# PentaBlinky.net
KiCad netlist of a schematic drawn in EAGLE
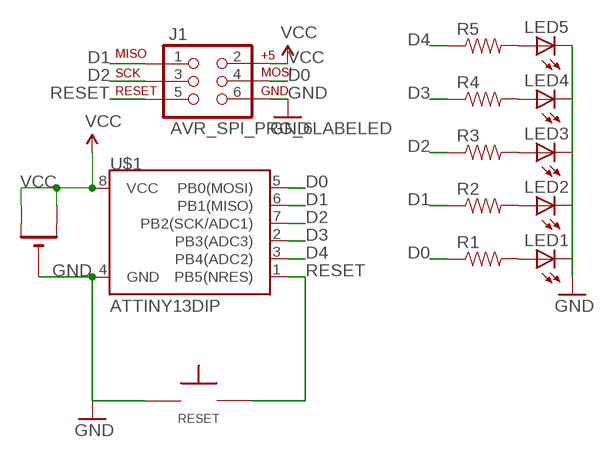
[diagram p0: schematic, sheet 1]

(export (version "E")
  (design (tool "Eeschema 10.0.6"))
  (components
    (comp (ref "J1")
      (value "AVR_SPI_PRG_6LABELED")
      (footprint "eagle-import:2X3-NS")
      (libsource (lib "eagle-import") (part "AVR_SPI_PRG_6LABELED"))
    )
    (comp (ref "LED1")
      (value "LED5MM")
      (footprint "eagle-import:LED5MM")
      (libsource (lib "eagle-import") (part "LED5MM"))
    )
    (comp (ref "LED2")
      (value "LED5MM")
      (footprint "eagle-import:LED5MM")
      (libsource (lib "eagle-import") (part "LED5MM"))
    )
    (comp (ref "LED3")
      (value "LED5MM")
      (footprint "eagle-import:LED5MM")
      (libsource (lib "eagle-import") (part "LED5MM"))
    )
    (comp (ref "LED4")
      (value "LED5MM")
      (footprint "eagle-import:LED5MM")
      (libsource (lib "eagle-import") (part "LED5MM"))
    )
    (comp (ref "LED5")
      (value "LED5MM")
      (footprint "eagle-import:LED5MM")
      (libsource (lib "eagle-import") (part "LED5MM"))
    )
    (comp (ref "R1")
      (value "RESISTORAXIAL-0.3")
      (footprint "eagle-import:AXIAL-0.3")
      (libsource (lib "eagle-import") (part "RESISTORAXIAL-0.3"))
    )
    (comp (ref "R2")
      (value "RESISTORAXIAL-0.3")
      (footprint "eagle-import:AXIAL-0.3")
      (libsource (lib "eagle-import") (part "RESISTORAXIAL-0.3"))
    )
    (comp (ref "R3")
      (value "RESISTORAXIAL-0.3")
      (footprint "eagle-import:AXIAL-0.3")
      (libsource (lib "eagle-import") (part "RESISTORAXIAL-0.3"))
    )
    (comp (ref "R4")
      (value "RESISTORAXIAL-0.3")
      (footprint "eagle-import:AXIAL-0.3")
      (libsource (lib "eagle-import") (part "RESISTORAXIAL-0.3"))
    )
    (comp (ref "R5")
      (value "RESISTORAXIAL-0.3")
      (footprint "eagle-import:AXIAL-0.3")
      (libsource (lib "eagle-import") (part "RESISTORAXIAL-0.3"))
    )
    (comp (ref "RESET")
      (value "SPST_NO")
      (footprint "eagle-import:TAC_SPST_NO")
      (libsource (lib "eagle-import") (part "TAC_SPST_NO"))
    )
    (comp (ref "U$1")
      (value "ATTINY13DIP")
      (footprint "eagle-import:DIP08")
      (libsource (lib "eagle-import") (part "ATTINY13DIP"))
    )
    (comp (ref "U$4")
      (value "BATT_GEN")
      (footprint "eagle-import:AA-AAA")
      (libsource (lib "eagle-import") (part "BATT_GEN"))
    )
  )
  (nets
    (net (code "1") (name "/D0") (class "Default")
      (node (ref "J1") (pin "4") (pinfunction "MOSI_4") (pintype "passive"))
      (node (ref "R1") (pin "P$1") (pinfunction "1_P$1") (pintype "passive"))
      (node (ref "U$1") (pin "5") (pinfunction "PB0(MOSI)_5") (pintype "bidirectional"))
    )
    (net (code "2") (name "/D1") (class "Default")
      (node (ref "J1") (pin "1") (pinfunction "MISO_1") (pintype "passive"))
      (node (ref "R2") (pin "P$1") (pinfunction "1_P$1") (pintype "passive"))
      (node (ref "U$1") (pin "6") (pinfunction "PB1(MISO)_6") (pintype "bidirectional"))
    )
    (net (code "3") (name "/D2") (class "Default")
      (node (ref "J1") (pin "3") (pinfunction "SCK_3") (pintype "passive"))
      (node (ref "R3") (pin "P$1") (pinfunction "1_P$1") (pintype "passive"))
      (node (ref "U$1") (pin "7") (pinfunction "PB2(SCK/ADC1)_7") (pintype "bidirectional"))
    )
    (net (code "4") (name "/D3") (class "Default")
      (node (ref "R4") (pin "P$1") (pinfunction "1_P$1") (pintype "passive"))
      (node (ref "U$1") (pin "2") (pinfunction "PB3(ADC3)_2") (pintype "bidirectional"))
    )
    (net (code "5") (name "/D4") (class "Default")
      (node (ref "R5") (pin "P$1") (pinfunction "1_P$1") (pintype "passive"))
      (node (ref "U$1") (pin "3") (pinfunction "PB4(ADC2)_3") (pintype "bidirectional"))
    )
    (net (code "6") (name "/RESET") (class "Default")
      (node (ref "J1") (pin "5") (pinfunction "RST_5") (pintype "passive"))
      (node (ref "RESET") (pin "P$2") (pinfunction "P$2_P$2") (pintype "bidirectional"))
      (node (ref "U$1") (pin "1") (pinfunction "PB5(NRES)_1") (pintype "bidirectional"))
    )
    (net (code "7") (name "GND") (class "Default")
      (node (ref "J1") (pin "6") (pinfunction "GND_6") (pintype "passive"))
      (node (ref "LED1") (pin "K") (pinfunction "C_K") (pintype "passive"))
      (node (ref "LED2") (pin "K") (pinfunction "C_K") (pintype "passive"))
      (node (ref "LED3") (pin "K") (pinfunction "C_K") (pintype "passive"))
      (node (ref "LED4") (pin "K") (pinfunction "C_K") (pintype "passive"))
      (node (ref "LED5") (pin "K") (pinfunction "C_K") (pintype "passive"))
      (node (ref "RESET") (pin "P$1") (pinfunction "P$1_P$1") (pintype "bidirectional"))
      (node (ref "U$1") (pin "4") (pinfunction "GND_4") (pintype "bidirectional"))
      (node (ref "U$4") (pin "-") (pinfunction "-_-") (pintype "passive"))
    )
    (net (code "8") (name "Net-(R1-2)") (class "Default")
      (node (ref "LED1") (pin "A") (pinfunction "A_A") (pintype "passive"))
      (node (ref "R1") (pin "P$2") (pinfunction "2_P$2") (pintype "passive"))
    )
    (net (code "9") (name "Net-(R2-2)") (class "Default")
      (node (ref "LED2") (pin "A") (pinfunction "A_A") (pintype "passive"))
      (node (ref "R2") (pin "P$2") (pinfunction "2_P$2") (pintype "passive"))
    )
    (net (code "10") (name "Net-(R3-2)") (class "Default")
      (node (ref "LED3") (pin "A") (pinfunction "A_A") (pintype "passive"))
      (node (ref "R3") (pin "P$2") (pinfunction "2_P$2") (pintype "passive"))
    )
    (net (code "11") (name "Net-(R4-2)") (class "Default")
      (node (ref "LED4") (pin "A") (pinfunction "A_A") (pintype "passive"))
      (node (ref "R4") (pin "P$2") (pinfunction "2_P$2") (pintype "passive"))
    )
    (net (code "12") (name "Net-(R5-2)") (class "Default")
      (node (ref "LED5") (pin "A") (pinfunction "A_A") (pintype "passive"))
      (node (ref "R5") (pin "P$2") (pinfunction "2_P$2") (pintype "passive"))
    )
    (net (code "13") (name "VCC") (class "Default")
      (node (ref "J1") (pin "2") (pinfunction "V+_2") (pintype "passive"))
      (node (ref "U$1") (pin "8") (pinfunction "VCC_8") (pintype "bidirectional"))
      (node (ref "U$4") (pin "+") (pinfunction "+_+") (pintype "passive"))
      (node (ref "U$4") (pin "++") (pinfunction "+1_++") (pintype "passive"))
    )
  )
)
